# pay-ssm.net
KiCad netlist of a schematic drawn in Altium Designer
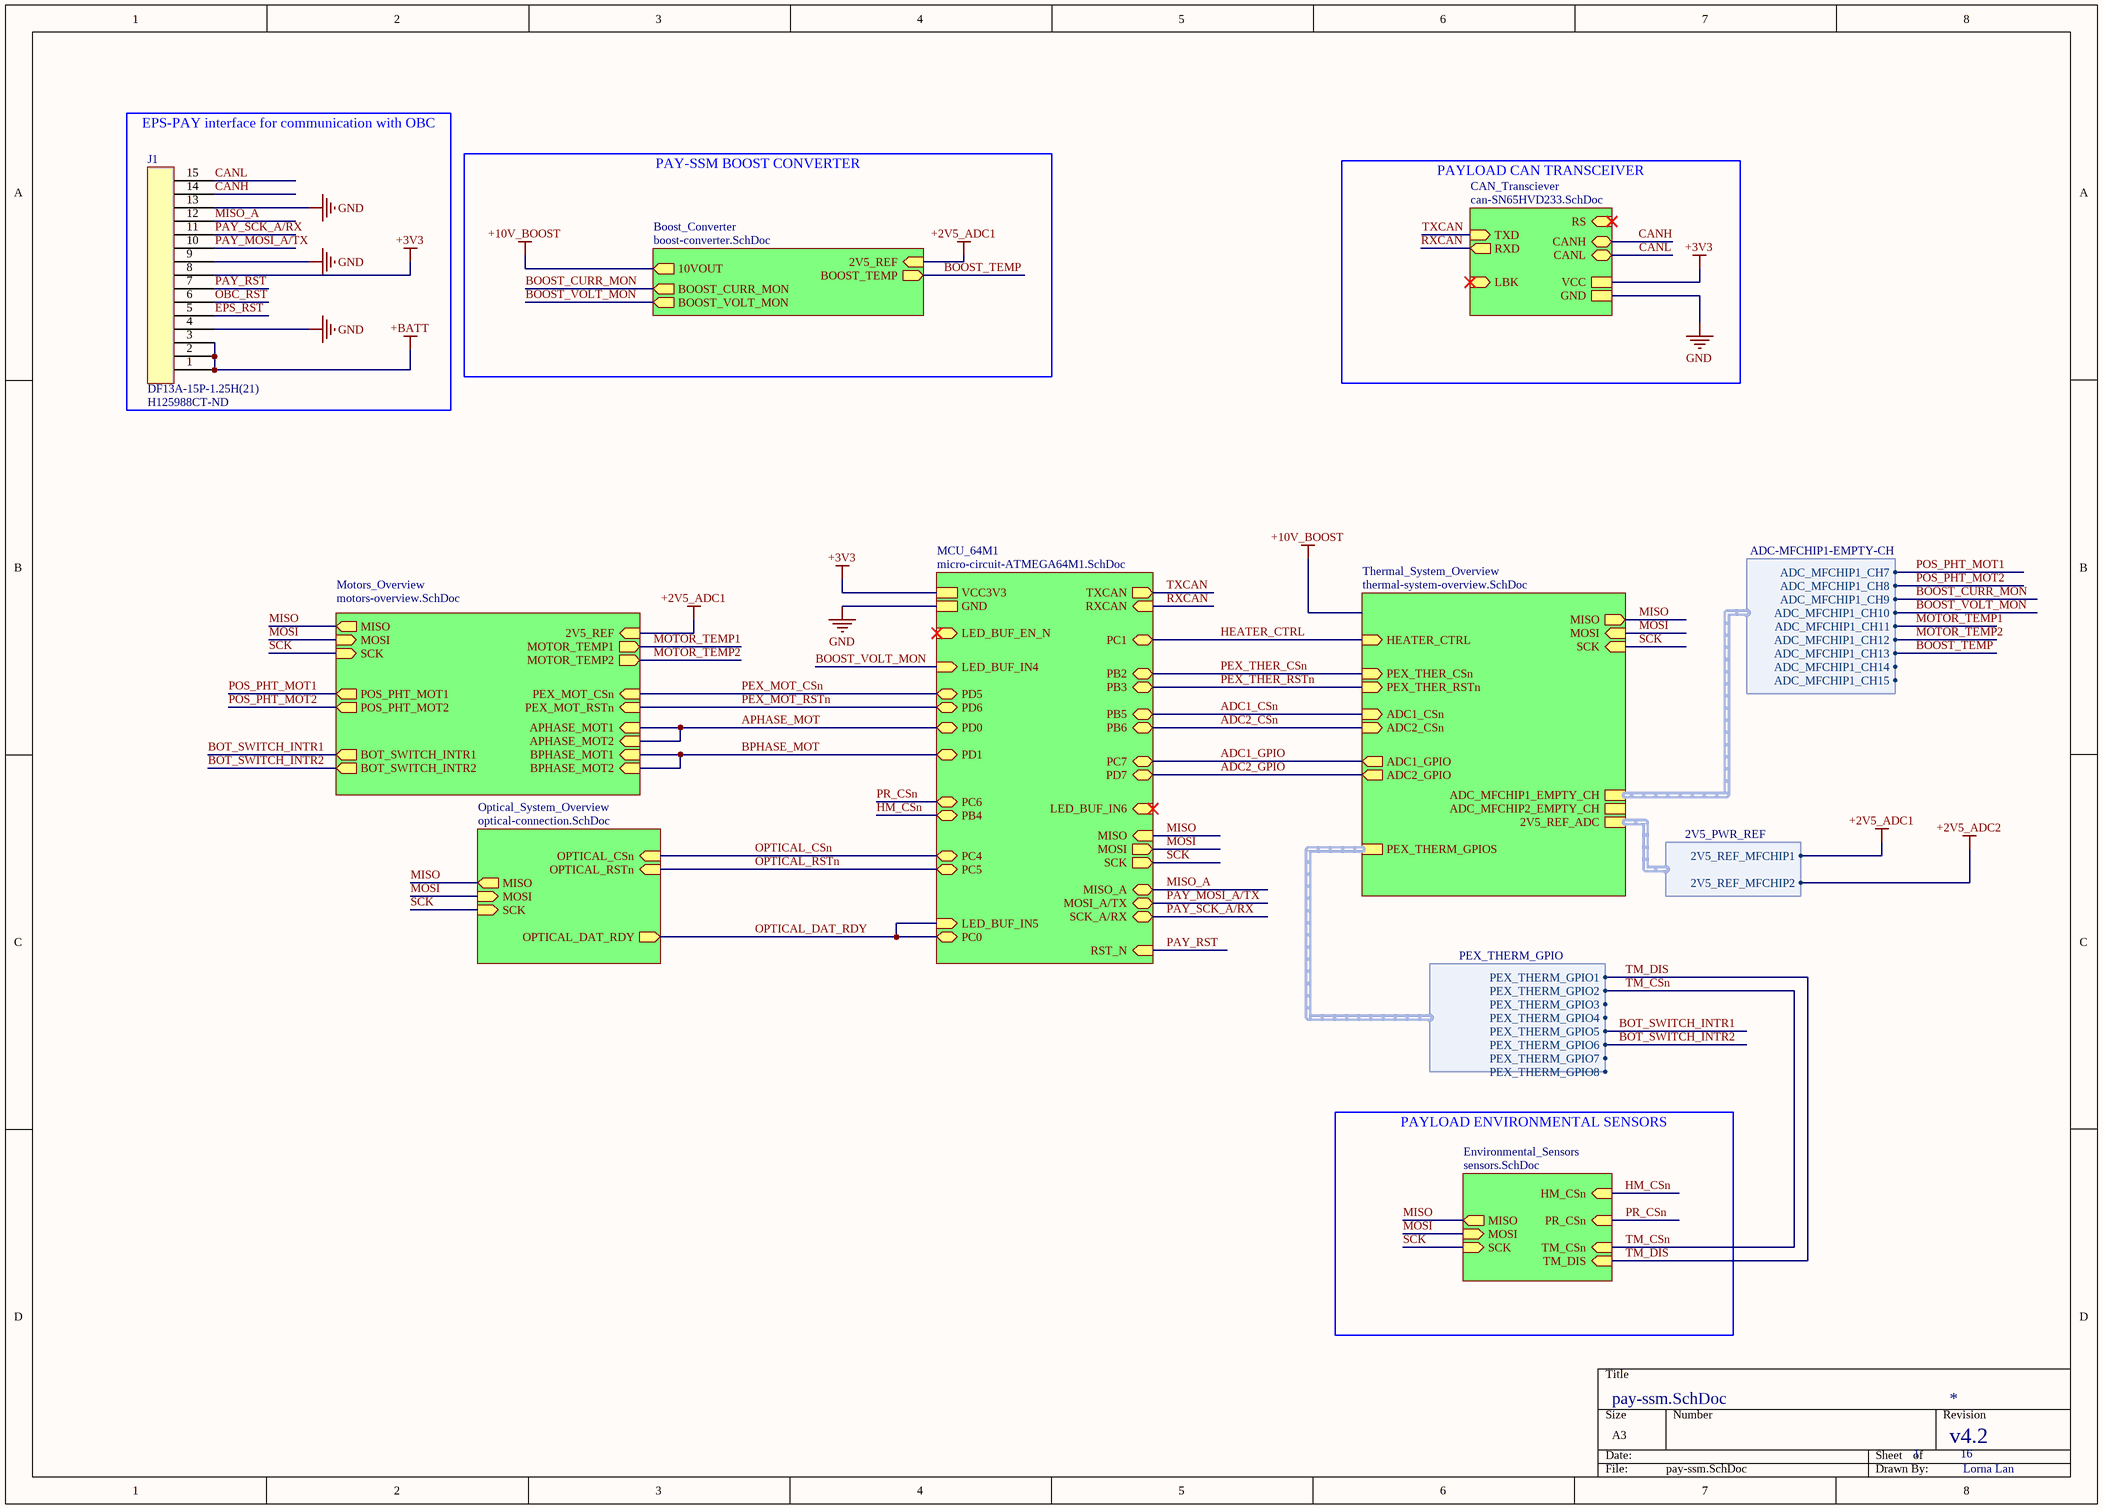
[diagram p0: pay-ssm.SchDoc]

(export (version "E")
  (design (tool "Eeschema 10.0.6"))
  (components
    (comp (ref "J1")
      (value "DF13A-15P-1.25H(21)")
      (footprint "DF13A-15P-1.25H(21)")
      (description "15 pos DF13 right angle surface mount connector")
      (fields (field (name "SUPPLIER PART NUMBER 1") "H125988CT-ND"))
      (libsource (lib "DF13A-15P-1.25H(21)") (part "DF13A-15P-1.25H(21)"))
    )
  )
  (nets
    (net (code "6") (name "+3V3") (class "Default") (node (ref "J1") (pin "8") (pintype "passive")))
    (net (code "8") (name "+BATT") (class "Default")
      (node (ref "J1") (pin "1") (pintype "passive"))
      (node (ref "J1") (pin "2") (pintype "passive"))
      (node (ref "J1") (pin "3") (pintype "passive"))
    )
    (net (code "22") (name "/CANH") (class "Default") (node (ref "J1") (pin "14") (pintype "passive")))
    (net (code "23") (name "/CANL") (class "Default") (node (ref "J1") (pin "15") (pintype "passive")))
    (net (code "24") (name "/EPS_RST") (class "Default") (node (ref "J1") (pin "5") (pintype "passive")))
    (net (code "31") (name "/MISO_A") (class "Default") (node (ref "J1") (pin "12") (pintype "passive")))
    (net (code "33") (name "/OBC_RST") (class "Default") (node (ref "J1") (pin "6") (pintype "passive")))
    (net (code "37") (name "/PAY_MOSI_A{slash}TX") (class "Default")
      (node (ref "J1") (pin "10") (pintype "passive"))
    )
    (net (code "38") (name "/PAY_RST") (class "Default") (node (ref "J1") (pin "7") (pintype "passive")))
    (net (code "39") (name "/PAY_SCK_A{slash}RX") (class "Default")
      (node (ref "J1") (pin "11") (pintype "passive"))
    )
    (net (code "56") (name "GND") (class "Default")
      (node (ref "J1") (pin "13") (pintype "passive"))
      (node (ref "J1") (pin "4") (pintype "passive"))
      (node (ref "J1") (pin "9") (pintype "passive"))
    )
  )
)
